# Signal-Isolation-Section.net
KiCad netlist of a schematic drawn in Altium Designer
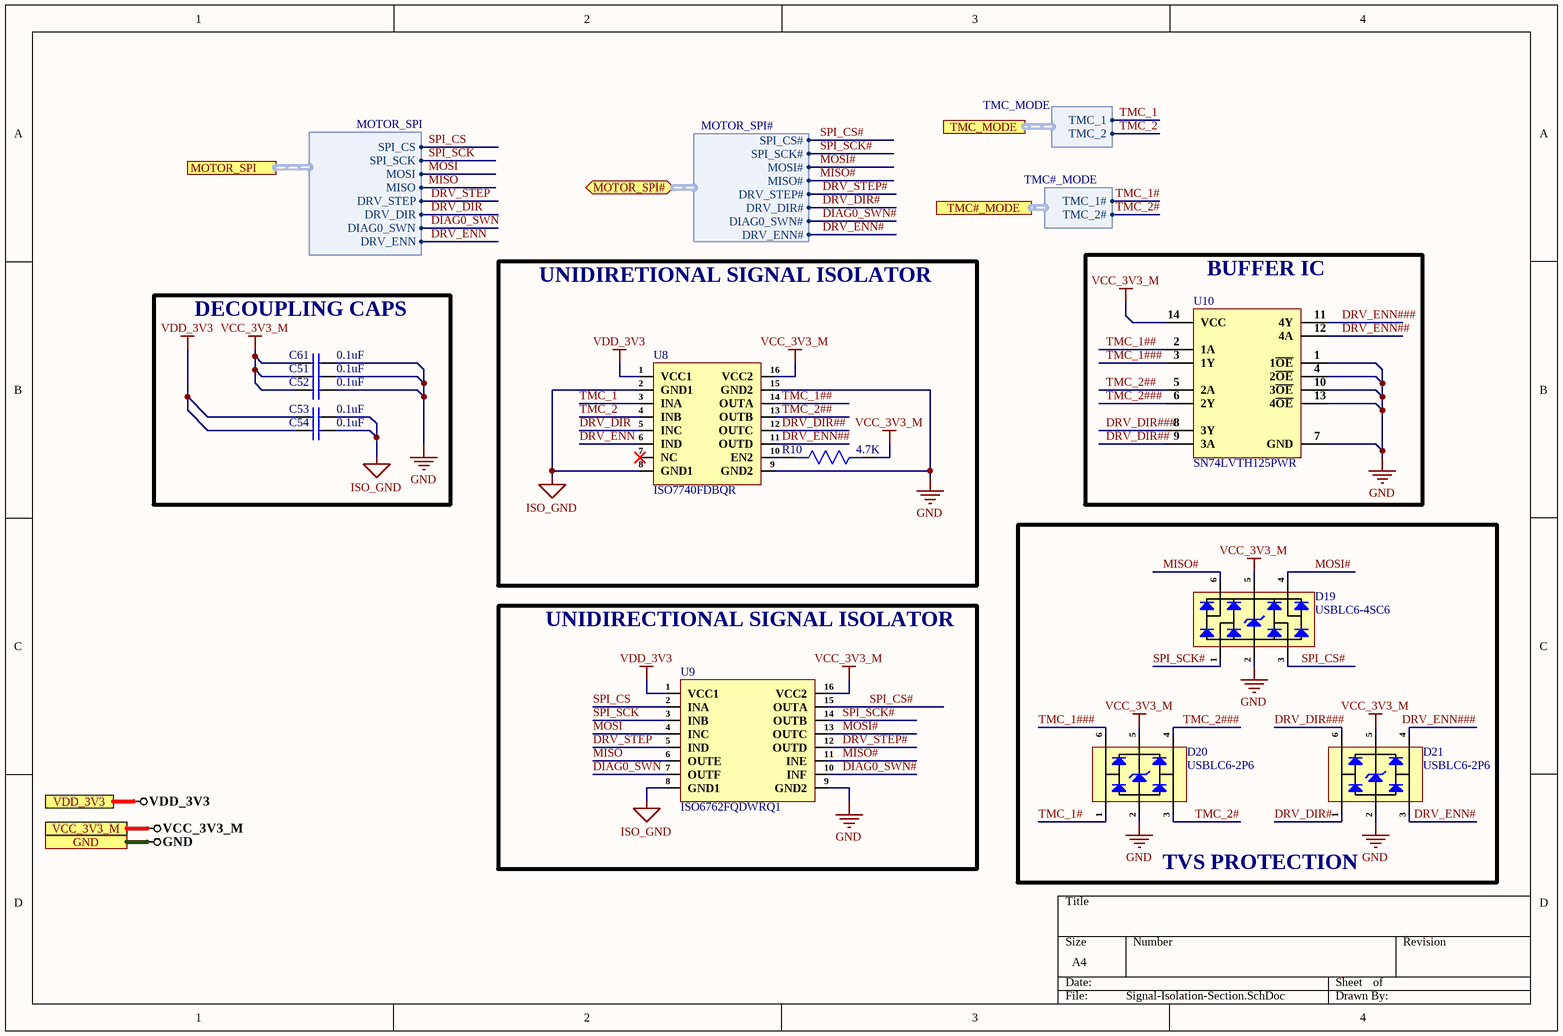
[diagram p0: Signal-Isolation-Section.SchDoc]

(export (version "E")
  (design (tool "Eeschema 10.0.6"))
  (components
    (comp (ref "C51")
      (value "0.1uF")
      (footprint "Cap 0603")
      (description "Cap Ceramic 0.1uF 50VDC X7R 10% SMD 0603 Paper T/R")
      (fields
        (field (name "MANUFACTURER") "Samsung")
        (field (name "MANUFACTURER PART NUMBER") "CL10B104KB8NNNC")
      )
      (libsource (lib "Cole_Benson") (part "CL10B104KB8NNNC"))
    )
    (comp (ref "C52")
      (value "0.1uF")
      (footprint "Cap 0603")
      (description "Cap Ceramic 0.1uF 50VDC X7R 10% SMD 0603 Paper T/R")
      (fields
        (field (name "MANUFACTURER") "Samsung")
        (field (name "MANUFACTURER PART NUMBER") "CL10B104KB8NNNC")
      )
      (libsource (lib "Cole_Benson") (part "CL10B104KB8NNNC"))
    )
    (comp (ref "C53")
      (value "0.1uF")
      (footprint "Cap 0603")
      (description "Cap Ceramic 0.1uF 50VDC X7R 10% SMD 0603 Paper T/R")
      (fields
        (field (name "MANUFACTURER") "Samsung")
        (field (name "MANUFACTURER PART NUMBER") "CL10B104KB8NNNC")
      )
      (libsource (lib "Cole_Benson") (part "CL10B104KB8NNNC"))
    )
    (comp (ref "C54")
      (value "0.1uF")
      (footprint "Cap 0603")
      (description "Cap Ceramic 0.1uF 50VDC X7R 10% SMD 0603 Paper T/R")
      (fields
        (field (name "MANUFACTURER") "Samsung")
        (field (name "MANUFACTURER PART NUMBER") "CL10B104KB8NNNC")
      )
      (libsource (lib "Cole_Benson") (part "CL10B104KB8NNNC"))
    )
    (comp (ref "C61")
      (value "0.1uF")
      (footprint "Cap 0603")
      (description "Cap Ceramic 0.1uF 50VDC X7R 10% SMD 0603 Paper T/R")
      (fields
        (field (name "MANUFACTURER") "Samsung")
        (field (name "MANUFACTURER PART NUMBER") "CL10B104KB8NNNC")
      )
      (libsource (lib "Cole_Benson") (part "CL10B104KB8NNNC"))
    )
    (comp (ref "D19")
      (value "USBLC6-4SC6")
      (footprint "SOT-23-6")
      (description "TVS DIODE 5.25VWM 17VC SOT23-6")
      (fields (field (name "LCSC PART NUMBER") "C111212"))
      (libsource (lib "eSpark Libraries") (part "USBLC6-4SC6"))
    )
    (comp (ref "D20")
      (value "USBLC6-2P6")
      (footprint "SOT-666")
      (description "TVS DIODE 5.25VWM 17VC SOT666")
      (fields (field (name "LCSC PART NUMBER") "C15999"))
      (libsource (lib "Cole_Benson") (part "USBLC6-2P6"))
    )
    (comp (ref "D21")
      (value "USBLC6-2P6")
      (footprint "SOT-666")
      (description "TVS DIODE 5.25VWM 17VC SOT666")
      (fields (field (name "LCSC PART NUMBER") "C15999"))
      (libsource (lib "Cole_Benson") (part "USBLC6-2P6"))
    )
    (comp (ref "R10")
      (value "4.7K")
      (footprint "Res-0201")
      (description "RES SMD 4.7K OHM 1% 1/20W 0201")
      (fields
        (field (name "MANUFACTURER") "Yageo")
        (field (name "MANUFACTURER PART NUMBER") "RC0201FR-074K7L")
      )
      (libsource (lib "Cole_Benson") (part "RC0201FR-074K7L"))
    )
    (comp (ref "U8")
      (value "ISO7740FDBQR")
      (footprint "16-SSOP")
      (description "DGTL ISO 3000VRMS 4CH GP 16SSOP")
      (fields (field (name "LCSC PART NUMBER") "C544482"))
      (libsource (lib "Cole_Benson") (part "ISO7740FDBQR"))
    )
    (comp (ref "U9")
      (value "ISO6762FQDWRQ1")
      (footprint "16-SOIC")
      (description "AUTOMOTIVE, GENERAL-PURPOSE, 50-")
      (fields (field (name "LCSC PART NUMBER") "C5216383"))
      (libsource (lib "Cole_Benson") (part "ISO6762FQDWRQ1"))
    )
    (comp (ref "U10")
      (value "SN74LVTH125PWR")
      (footprint "SN74LVTH125PWR")
      (description "IC BUS BUFFER TRI-ST QD 14TSSOP")
      (fields (field (name "MANUFACTURER") "Texas Instruments"))
      (libsource (lib "Cole_Benson") (part "SN74LVTH125PWR"))
    )
  )
  (nets
    (net (code "5") (name "/DIAG0_SWN") (class "Default")
      (node (ref "U9") (pin "7") (pinfunction "OUTF_7") (pintype "passive"))
    )
    (net (code "6") (name "/DIAG0_SWN#") (class "Default")
      (node (ref "U9") (pin "10") (pinfunction "INF_10") (pintype "passive"))
    )
    (net (code "7") (name "/DRV_DIR") (class "Default")
      (node (ref "U8") (pin "5") (pinfunction "INC_5") (pintype "passive"))
    )
    (net (code "8") (name "/DRV_DIR#") (class "Default")
      (node (ref "D21") (pin "1") (pinfunction "I/O1_1") (pintype "passive"))
    )
    (net (code "9") (name "/DRV_DIR##") (class "Default")
      (node (ref "U10") (pin "9") (pinfunction "3A_9") (pintype "passive"))
      (node (ref "U8") (pin "12") (pinfunction "OUTC_12") (pintype "passive"))
    )
    (net (code "10") (name "/DRV_DIR###") (class "Default")
      (node (ref "D21") (pin "6") (pinfunction "I/O1_6") (pintype "passive"))
      (node (ref "U10") (pin "8") (pinfunction "3Y_8") (pintype "passive"))
    )
    (net (code "11") (name "/DRV_ENN") (class "Default")
      (node (ref "U8") (pin "6") (pinfunction "IND_6") (pintype "passive"))
    )
    (net (code "12") (name "/DRV_ENN#") (class "Default")
      (node (ref "D21") (pin "3") (pinfunction "I/O2_3") (pintype "passive"))
    )
    (net (code "13") (name "/DRV_ENN##") (class "Default")
      (node (ref "U10") (pin "12") (pinfunction "4A_12") (pintype "passive"))
      (node (ref "U8") (pin "11") (pinfunction "OUTD_11") (pintype "passive"))
    )
    (net (code "14") (name "/DRV_ENN###") (class "Default")
      (node (ref "D21") (pin "4") (pinfunction "I/O2_4") (pintype "passive"))
      (node (ref "U10") (pin "11") (pinfunction "4Y_11") (pintype "passive"))
    )
    (net (code "15") (name "/DRV_STEP") (class "Default")
      (node (ref "U9") (pin "5") (pinfunction "IND_5") (pintype "passive"))
    )
    (net (code "16") (name "/DRV_STEP#") (class "Default")
      (node (ref "U9") (pin "12") (pinfunction "OUTD_12") (pintype "passive"))
    )
    (net (code "17") (name "/MISO") (class "Default")
      (node (ref "U9") (pin "6") (pinfunction "OUTE_6") (pintype "passive"))
    )
    (net (code "18") (name "/MISO#") (class "Default")
      (node (ref "D19") (pin "6") (pinfunction "I/O4_6") (pintype "passive"))
      (node (ref "U9") (pin "11") (pinfunction "INE_11") (pintype "passive"))
    )
    (net (code "19") (name "/MOSI") (class "Default")
      (node (ref "U9") (pin "4") (pinfunction "INC_4") (pintype "passive"))
    )
    (net (code "20") (name "/MOSI#") (class "Default")
      (node (ref "D19") (pin "4") (pinfunction "I/O3_4") (pintype "passive"))
      (node (ref "U9") (pin "13") (pinfunction "OUTC_13") (pintype "passive"))
    )
    (net (code "21") (name "/SPI_CS") (class "Default")
      (node (ref "U9") (pin "2") (pinfunction "INA_2") (pintype "passive"))
    )
    (net (code "22") (name "/SPI_CS#") (class "Default")
      (node (ref "D19") (pin "3") (pinfunction "I/O2_3") (pintype "passive"))
      (node (ref "U9") (pin "15") (pinfunction "OUTA_15") (pintype "passive"))
    )
    (net (code "23") (name "/SPI_SCK") (class "Default")
      (node (ref "U9") (pin "3") (pinfunction "INB_3") (pintype "passive"))
    )
    (net (code "24") (name "/SPI_SCK#") (class "Default")
      (node (ref "D19") (pin "1") (pinfunction "I/O1_1") (pintype "passive"))
      (node (ref "U9") (pin "14") (pinfunction "OUTB_14") (pintype "passive"))
    )
    (net (code "25") (name "/TMC_1") (class "Default")
      (node (ref "U8") (pin "3") (pinfunction "INA_3") (pintype "passive"))
    )
    (net (code "26") (name "/TMC_1#") (class "Default")
      (node (ref "D20") (pin "1") (pinfunction "I/O1_1") (pintype "passive"))
    )
    (net (code "27") (name "/TMC_1##") (class "Default")
      (node (ref "U10") (pin "2") (pinfunction "1A_2") (pintype "passive"))
      (node (ref "U8") (pin "14") (pinfunction "OUTA_14") (pintype "passive"))
    )
    (net (code "28") (name "/TMC_1###") (class "Default")
      (node (ref "D20") (pin "6") (pinfunction "I/O1_6") (pintype "passive"))
      (node (ref "U10") (pin "3") (pinfunction "1Y_3") (pintype "passive"))
    )
    (net (code "29") (name "/TMC_2") (class "Default")
      (node (ref "U8") (pin "4") (pinfunction "INB_4") (pintype "passive"))
    )
    (net (code "30") (name "/TMC_2#") (class "Default")
      (node (ref "D20") (pin "3") (pinfunction "I/O2_3") (pintype "passive"))
    )
    (net (code "31") (name "/TMC_2##") (class "Default")
      (node (ref "U10") (pin "5") (pinfunction "2A_5") (pintype "passive"))
      (node (ref "U8") (pin "13") (pinfunction "OUTB_13") (pintype "passive"))
    )
    (net (code "32") (name "/TMC_2###") (class "Default")
      (node (ref "D20") (pin "4") (pinfunction "I/O2_4") (pintype "passive"))
      (node (ref "U10") (pin "6") (pinfunction "2Y_6") (pintype "passive"))
    )
    (net (code "37") (name "GND") (class "Default")
      (node (ref "C51") (pin "2") (pinfunction "2_2") (pintype "passive"))
      (node (ref "C52") (pin "2") (pinfunction "2_2") (pintype "passive"))
      (node (ref "C61") (pin "2") (pinfunction "2_2") (pintype "passive"))
      (node (ref "D19") (pin "2") (pinfunction "GND_2") (pintype "passive"))
      (node (ref "D20") (pin "2") (pinfunction "GND_2") (pintype "passive"))
      (node (ref "D21") (pin "2") (pinfunction "GND_2") (pintype "passive"))
      (node (ref "U10") (pin "1") (pinfunction "1~{OE}_1") (pintype "passive"))
      (node (ref "U10") (pin "10") (pinfunction "3~{OE}_10") (pintype "passive"))
      (node (ref "U10") (pin "13") (pinfunction "4~{OE}_13") (pintype "passive"))
      (node (ref "U10") (pin "4") (pinfunction "2~{OE}_4") (pintype "passive"))
      (node (ref "U10") (pin "7") (pinfunction "GND_7") (pintype "passive"))
      (node (ref "U8") (pin "15") (pinfunction "GND2_15") (pintype "passive"))
      (node (ref "U8") (pin "9") (pinfunction "GND2_9") (pintype "passive"))
      (node (ref "U9") (pin "9") (pinfunction "GND2_9") (pintype "passive"))
    )
    (net (code "38") (name "ISO_GND") (class "Default")
      (node (ref "C53") (pin "2") (pinfunction "2_2") (pintype "passive"))
      (node (ref "C54") (pin "2") (pinfunction "2_2") (pintype "passive"))
      (node (ref "U8") (pin "2") (pinfunction "GND1_2") (pintype "passive"))
      (node (ref "U8") (pin "8") (pinfunction "GND1_8") (pintype "passive"))
      (node (ref "U9") (pin "8") (pinfunction "GND1_8") (pintype "passive"))
    )
    (net (code "39") (name "Net-(U8-EN2)") (class "Default")
      (node (ref "R10") (pin "2") (pintype "passive"))
      (node (ref "U8") (pin "10") (pinfunction "EN2_10") (pintype "passive"))
    )
    (net (code "40") (name "VCC_3V3_M") (class "Default")
      (node (ref "C51") (pin "1") (pinfunction "1_1") (pintype "passive"))
      (node (ref "C52") (pin "1") (pinfunction "1_1") (pintype "passive"))
      (node (ref "C61") (pin "1") (pinfunction "1_1") (pintype "passive"))
      (node (ref "D19") (pin "5") (pinfunction "VBUS_5") (pintype "passive"))
      (node (ref "D20") (pin "5") (pinfunction "VBUS_5") (pintype "passive"))
      (node (ref "D21") (pin "5") (pinfunction "VBUS_5") (pintype "passive"))
      (node (ref "R10") (pin "1") (pintype "passive"))
      (node (ref "U10") (pin "14") (pinfunction "VCC_14") (pintype "passive"))
      (node (ref "U8") (pin "16") (pinfunction "VCC2_16") (pintype "passive"))
      (node (ref "U9") (pin "16") (pinfunction "VCC2_16") (pintype "passive"))
    )
    (net (code "41") (name "VDD_3V3") (class "Default")
      (node (ref "C53") (pin "1") (pinfunction "1_1") (pintype "passive"))
      (node (ref "C54") (pin "1") (pinfunction "1_1") (pintype "passive"))
      (node (ref "U8") (pin "1") (pinfunction "VCC1_1") (pintype "passive"))
      (node (ref "U9") (pin "1") (pinfunction "VCC1_1") (pintype "passive"))
    )
    (net (code "42") (name "unconnected-(U8-NC-Pad7)") (class "Default")
      (node (ref "U8") (pin "7") (pinfunction "NC_7") (pintype "passive+no_connect"))
    )
  )
)
